# WA-ES_p1_twoside.net
KiCad netlist of a schematic drawn in EAGLE
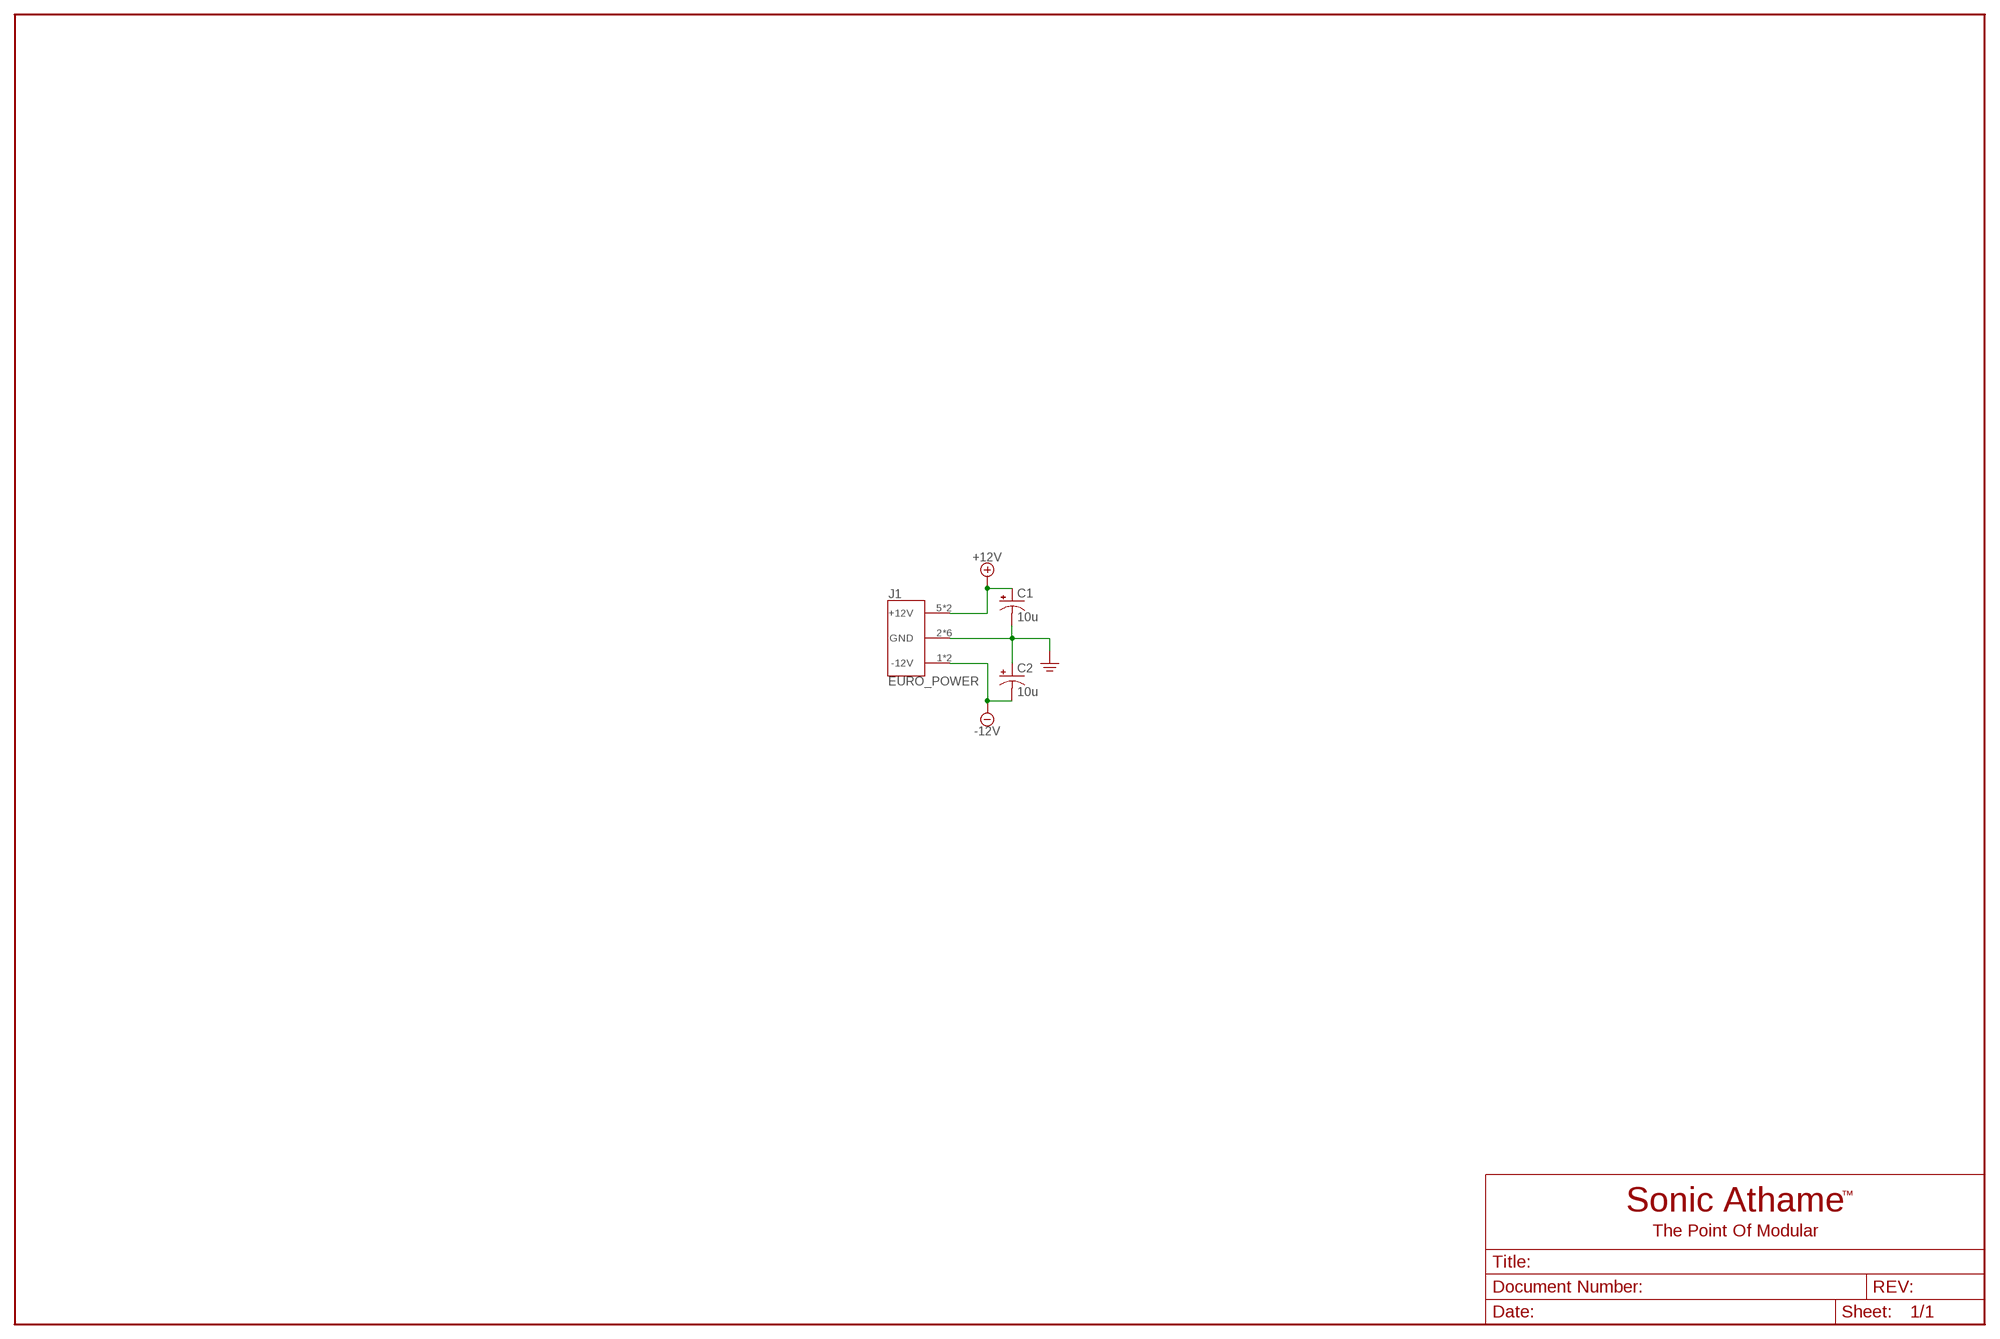
[diagram p0: schematic, sheet 1]

(export (version "E")
  (design (tool "Eeschema 10.0.6"))
  (components
    (comp (ref "C1")
      (value "10u")
      (footprint "eagle-import:TT2D5")
      (libsource (lib "eagle-import") (part "CAP_POLLYTIC_V"))
    )
    (comp (ref "C2")
      (value "10u")
      (footprint "eagle-import:TT2D5")
      (libsource (lib "eagle-import") (part "CAP_POLLYTIC_V"))
    )
    (comp (ref "J1")
      (value "EURO_POWER")
      (footprint "eagle-import:EURO_POWER")
      (libsource (lib "eagle-import") (part "EURO_POWER"))
    )
  )
  (nets
    (net (code "1") (name "+12V") (class "Default")
      (node (ref "C1") (pin "+") (pinfunction "+_+") (pintype "passive"))
      (node (ref "J1") (pin "5") (pinfunction "+12V_5") (pintype "bidirectional"))
      (node (ref "J1") (pin "6") (pinfunction "+12V_6") (pintype "bidirectional"))
    )
    (net (code "2") (name "-12V") (class "Default")
      (node (ref "C2") (pin "-") (pinfunction "-_-") (pintype "passive"))
      (node (ref "J1") (pin "1") (pinfunction "-12V_1") (pintype "bidirectional"))
      (node (ref "J1") (pin "10") (pinfunction "-12V_10") (pintype "bidirectional"))
    )
    (net (code "3") (name "GND") (class "Default")
      (node (ref "C1") (pin "-") (pinfunction "-_-") (pintype "passive"))
      (node (ref "C2") (pin "+") (pinfunction "+_+") (pintype "passive"))
      (node (ref "J1") (pin "2") (pinfunction "GND_2") (pintype "bidirectional"))
      (node (ref "J1") (pin "3") (pinfunction "GND_3") (pintype "bidirectional"))
      (node (ref "J1") (pin "4") (pinfunction "GND_4") (pintype "bidirectional"))
      (node (ref "J1") (pin "7") (pinfunction "GND_7") (pintype "bidirectional"))
      (node (ref "J1") (pin "8") (pinfunction "GND_8") (pintype "bidirectional"))
      (node (ref "J1") (pin "9") (pinfunction "GND_9") (pintype "bidirectional"))
    )
  )
)
